# ShutdownLoop.net
KiCad netlist of a schematic drawn in Altium Designer
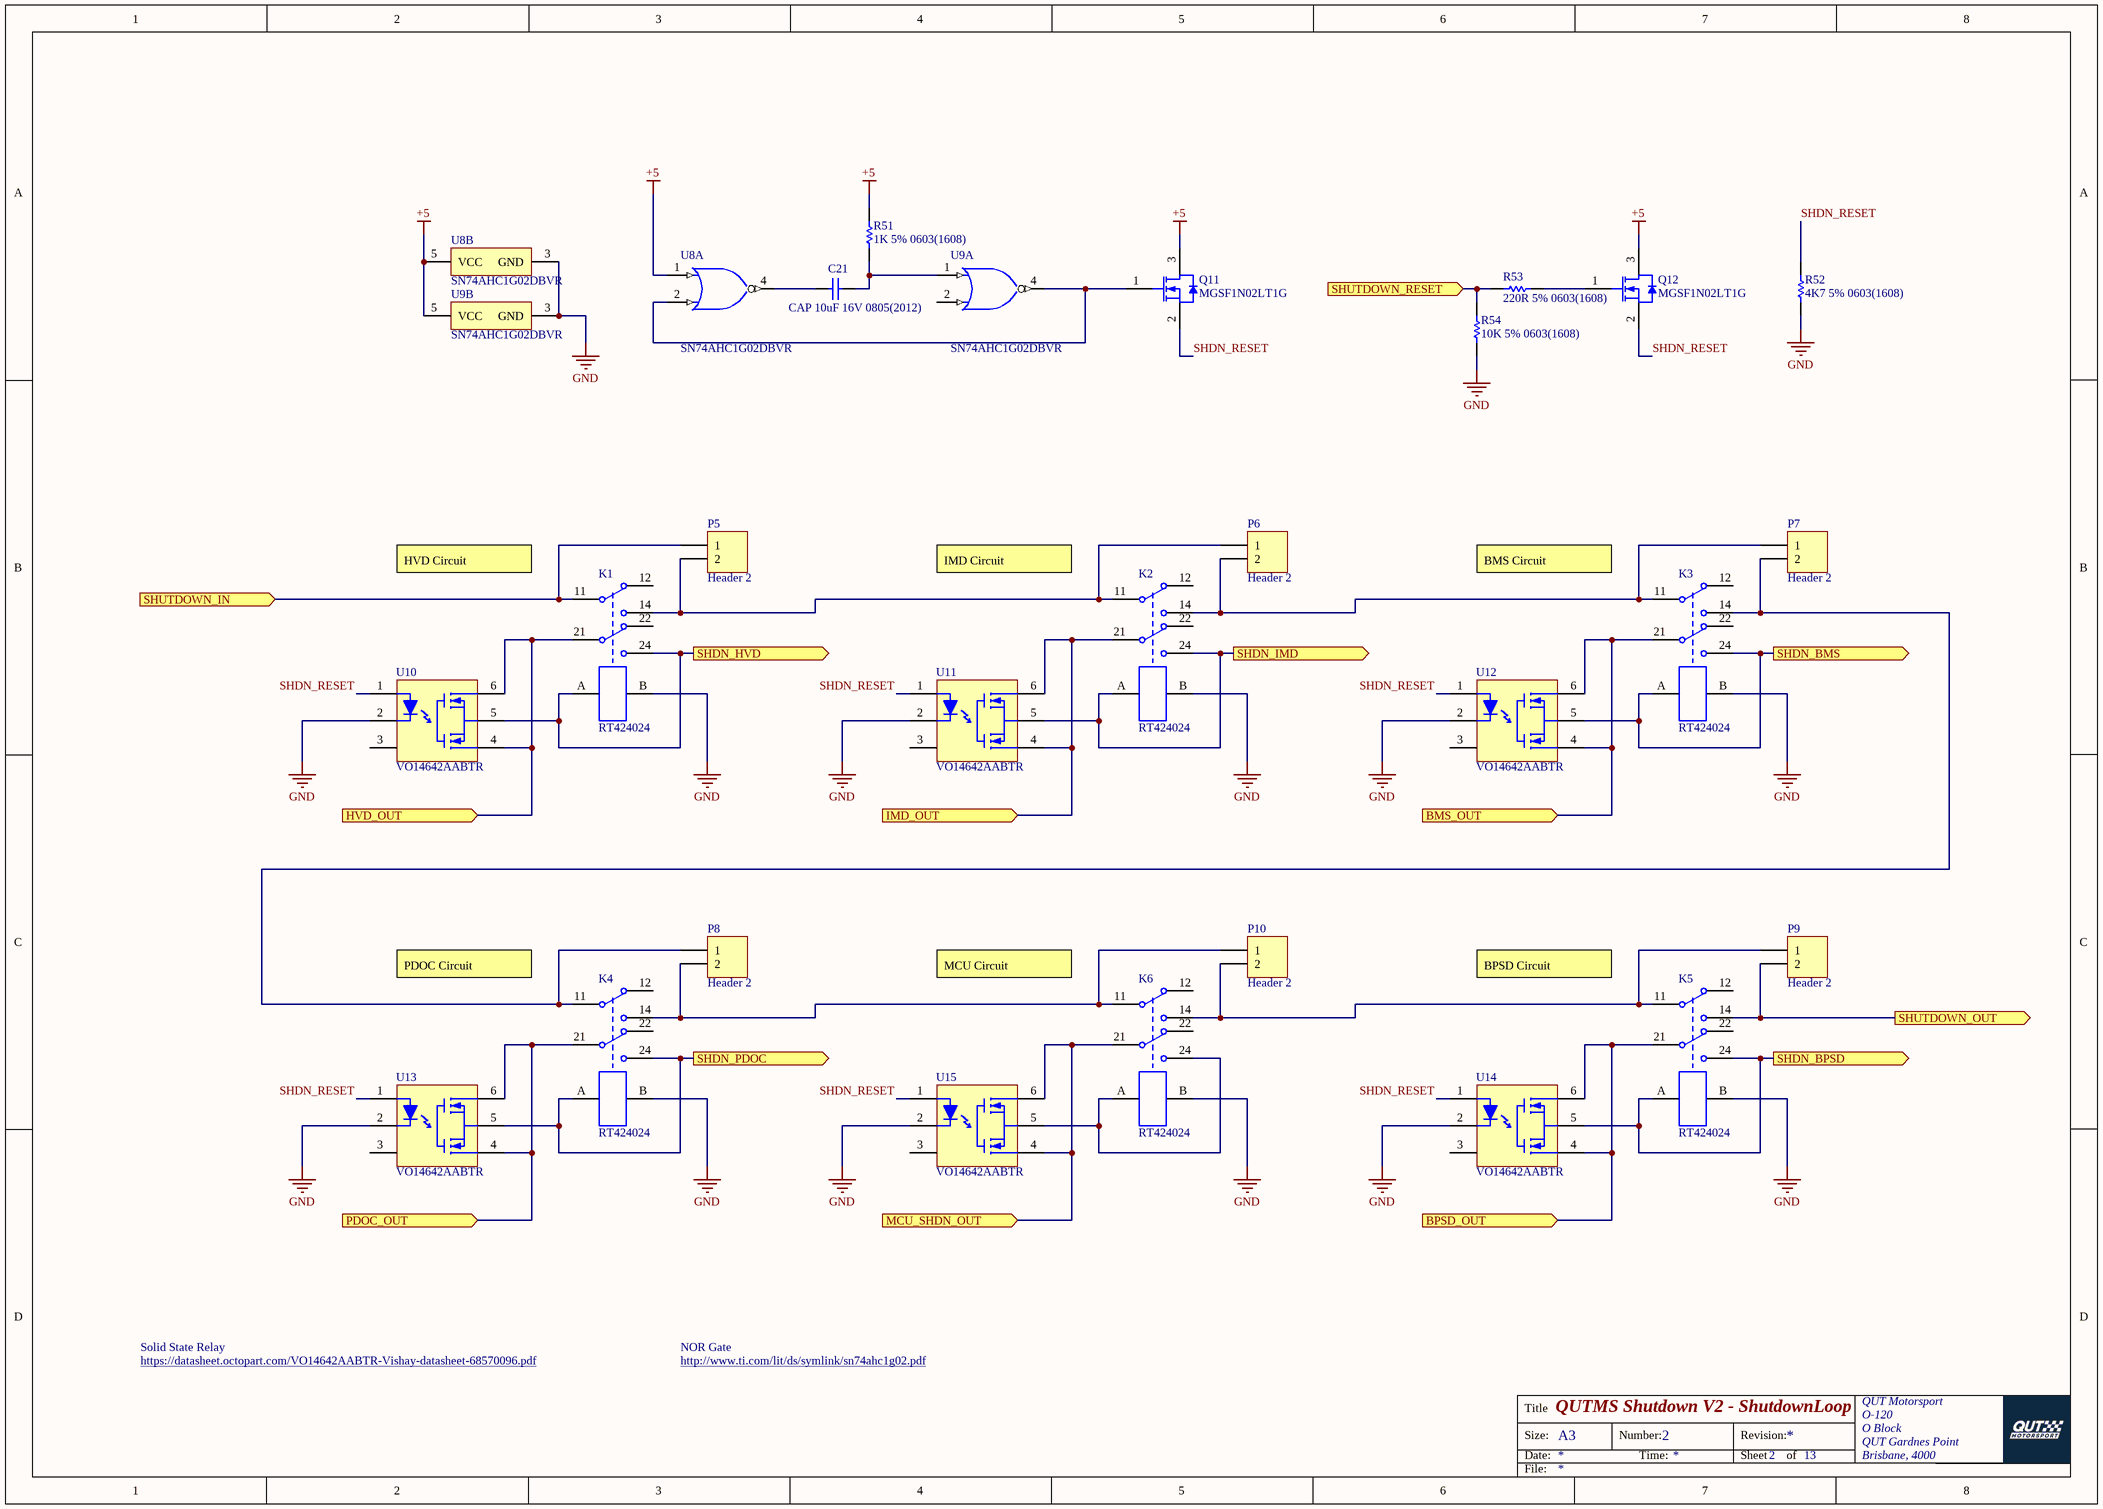
[diagram p0: ShutdownLoop.SchDoc]

(export (version "E")
  (design (tool "Eeschema 10.0.6"))
  (components
    (comp (ref "C21")
      (value "CAP 10uF 16V 0805(2012)")
      (footprint "CAPC0805(2012)100_L")
      (description "CAP 10uF 16V ±10% 0805 (2012 Metric) Thickness 1mm SMD")
      (fields (field (name "TOLERANCE") "Â±10%"))
      (libsource (lib "Altium Content Vault") (part "CAP"))
    )
    (comp (ref "K1")
      (value "RT424024")
      (footprint "TECO-RT424024_V")
      (description "DPDT 2 Form C (CO) Low Power PCB Relay, 24 VDC, 8 A, -40 to 85 degC, 8-Pin THD, RoHS, Tube")
      (fields (field (name "MANUFACTURER") "TE Connectivity"))
      (libsource (lib "Altium Content Vault") (part "RELAY-DPDT-8"))
    )
    (comp (ref "K2")
      (value "RT424024")
      (footprint "TECO-RT424024_V")
      (description "DPDT 2 Form C (CO) Low Power PCB Relay, 24 VDC, 8 A, -40 to 85 degC, 8-Pin THD, RoHS, Tube")
      (fields (field (name "MANUFACTURER") "TE Connectivity"))
      (libsource (lib "Altium Content Vault") (part "RELAY-DPDT-8"))
    )
    (comp (ref "K3")
      (value "RT424024")
      (footprint "TECO-RT424024_V")
      (description "DPDT 2 Form C (CO) Low Power PCB Relay, 24 VDC, 8 A, -40 to 85 degC, 8-Pin THD, RoHS, Tube")
      (fields (field (name "MANUFACTURER") "TE Connectivity"))
      (libsource (lib "Altium Content Vault") (part "RELAY-DPDT-8"))
    )
    (comp (ref "K4")
      (value "RT424024")
      (footprint "TECO-RT424024_V")
      (description "DPDT 2 Form C (CO) Low Power PCB Relay, 24 VDC, 8 A, -40 to 85 degC, 8-Pin THD, RoHS, Tube")
      (fields (field (name "MANUFACTURER") "TE Connectivity"))
      (libsource (lib "Altium Content Vault") (part "RELAY-DPDT-8"))
    )
    (comp (ref "K5")
      (value "RT424024")
      (footprint "TECO-RT424024_V")
      (description "DPDT 2 Form C (CO) Low Power PCB Relay, 24 VDC, 8 A, -40 to 85 degC, 8-Pin THD, RoHS, Tube")
      (fields (field (name "MANUFACTURER") "TE Connectivity"))
      (libsource (lib "Altium Content Vault") (part "RELAY-DPDT-8"))
    )
    (comp (ref "K6")
      (value "RT424024")
      (footprint "TECO-RT424024_V")
      (description "DPDT 2 Form C (CO) Low Power PCB Relay, 24 VDC, 8 A, -40 to 85 degC, 8-Pin THD, RoHS, Tube")
      (fields (field (name "MANUFACTURER") "TE Connectivity"))
      (libsource (lib "Altium Content Vault") (part "RELAY-DPDT-8"))
    )
    (comp (ref "P5")
      (value "Header 2")
      (footprint "HDR1X2")
      (description "Header, 2-Pin")
      (fields (field (name "PUBLISHER") "Altium Limited"))
      (libsource (lib "Miscellaneous Connectors") (part "Header 2"))
    )
    (comp (ref "P6")
      (value "Header 2")
      (footprint "HDR1X2")
      (description "Header, 2-Pin")
      (fields (field (name "PUBLISHER") "Altium Limited"))
      (libsource (lib "Miscellaneous Connectors") (part "Header 2"))
    )
    (comp (ref "P7")
      (value "Header 2")
      (footprint "HDR1X2")
      (description "Header, 2-Pin")
      (fields (field (name "PUBLISHER") "Altium Limited"))
      (libsource (lib "Miscellaneous Connectors") (part "Header 2"))
    )
    (comp (ref "P8")
      (value "Header 2")
      (footprint "HDR1X2")
      (description "Header, 2-Pin")
      (fields (field (name "PUBLISHER") "Altium Limited"))
      (libsource (lib "Miscellaneous Connectors") (part "Header 2"))
    )
    (comp (ref "P9")
      (value "Header 2")
      (footprint "HDR1X2")
      (description "Header, 2-Pin")
      (fields (field (name "PUBLISHER") "Altium Limited"))
      (libsource (lib "Miscellaneous Connectors") (part "Header 2"))
    )
    (comp (ref "P10")
      (value "Header 2")
      (footprint "HDR1X2")
      (description "Header, 2-Pin")
      (fields (field (name "PUBLISHER") "Altium Limited"))
      (libsource (lib "Miscellaneous Connectors") (part "Header 2"))
    )
    (comp (ref "Q11")
      (value "MGSF1N02LT1G")
      (footprint "ONSC-SOT-23-3-318-08_V")
      (description "Power MOSFET, 750 mA, 20 V, N-Channel, 3-Pin SOT-23, Pb-Free, Tape and Reel")
      (fields (field (name "MANUFACTURER") "On Semiconductor"))
      (libsource (lib "Altium Content Vault") (part "ONSC-NMOS-G1S2D3-3"))
    )
    (comp (ref "Q12")
      (value "MGSF1N02LT1G")
      (footprint "ONSC-SOT-23-3-318-08_V")
      (description "Power MOSFET, 750 mA, 20 V, N-Channel, 3-Pin SOT-23, Pb-Free, Tape and Reel")
      (fields (field (name "MANUFACTURER") "On Semiconductor"))
      (libsource (lib "Altium Content Vault") (part "ONSC-NMOS-G1S2D3-3"))
    )
    (comp (ref "R51")
      (value "1K 5% 0603(1608)")
      (footprint "RESC0603(1608)_L")
      (description "1K 0.1W 5% 0603 (1608 Metric)  SMD")
      (fields (field (name "TOLERANCE") "5 %") (field (name "POWER") "0.1 W"))
      (libsource (lib "Altium Content Vault") (part "RES"))
    )
    (comp (ref "R52")
      (value "4K7 5% 0603(1608)")
      (footprint "RESC0603(1608)_N")
      (description "4K7 0.1W 5% 0603 (1608 Metric)  SMD")
      (fields (field (name "TOLERANCE") "5 %") (field (name "POWER") "0.1 W"))
      (libsource (lib "Altium Content Vault") (part "RES"))
    )
    (comp (ref "R53")
      (value "220R 5% 0603(1608)")
      (footprint "RESC0603(1608)_M")
      (description "220R 0.1W 5% 0603 (1608 Metric)  SMD")
      (fields (field (name "POWER") "0.1 W") (field (name "TOLERANCE") "5 %"))
      (libsource (lib "Altium Content Vault") (part "RES"))
    )
    (comp (ref "R54")
      (value "10K 5% 0603(1608)")
      (footprint "RESC0603(1608)_N")
      (description "10K 0.1W 5% 0603 (1608 Metric)  SMD")
      (fields (field (name "TOLERANCE") "5 %") (field (name "POWER") "0.1 W"))
      (libsource (lib "Altium Content Vault") (part "RES"))
    )
    (comp (ref "U8")
      (value "SN74AHC1G02DBVR")
      (footprint "DBV0005A_L")
      (description "Single 2-Input Positive-NOR Gate, DBV0005A, LARGE T&R")
      (fields
        (field (name "MANUFACTURER") "Texas Instruments")
        (field (name "GENERIC PART NUMBER") "SN74AHC1G02")
      )
      (libsource (lib "Altium Content Vault") (part "TI-SN74XXX1X02-5"))
    )
    (comp (ref "U9")
      (value "SN74AHC1G02DBVR")
      (footprint "DBV0005A_L")
      (description "Single 2-Input Positive-NOR Gate, DBV0005A, LARGE T&R")
      (fields
        (field (name "MANUFACTURER") "Texas Instruments")
        (field (name "GENERIC PART NUMBER") "SN74AHC1G02")
      )
      (libsource (lib "Altium Content Vault") (part "TI-SN74XXX1X02-5"))
    )
    (comp (ref "U10")
      (value "VO14642AABTR")
      (footprint "VISH-VO14642AABTR_V")
      (description "1 Form A Solid State Relay, 2 A, -40 to 85 degC, 6-Pin SMD, RoHS, Tape and Reel")
      (fields (field (name "MANUFACTURER") "Vishay"))
      (libsource (lib "Altium Content Vault") (part "VISH-VO14642AABTR-6"))
    )
    (comp (ref "U11")
      (value "VO14642AABTR")
      (footprint "VISH-VO14642AABTR_V")
      (description "1 Form A Solid State Relay, 2 A, -40 to 85 degC, 6-Pin SMD, RoHS, Tape and Reel")
      (fields (field (name "MANUFACTURER") "Vishay"))
      (libsource (lib "Altium Content Vault") (part "VISH-VO14642AABTR-6"))
    )
    (comp (ref "U12")
      (value "VO14642AABTR")
      (footprint "VISH-VO14642AABTR_V")
      (description "1 Form A Solid State Relay, 2 A, -40 to 85 degC, 6-Pin SMD, RoHS, Tape and Reel")
      (fields (field (name "MANUFACTURER") "Vishay"))
      (libsource (lib "Altium Content Vault") (part "VISH-VO14642AABTR-6"))
    )
    (comp (ref "U13")
      (value "VO14642AABTR")
      (footprint "VISH-VO14642AABTR_V")
      (description "1 Form A Solid State Relay, 2 A, -40 to 85 degC, 6-Pin SMD, RoHS, Tape and Reel")
      (fields (field (name "MANUFACTURER") "Vishay"))
      (libsource (lib "Altium Content Vault") (part "VISH-VO14642AABTR-6"))
    )
    (comp (ref "U14")
      (value "VO14642AABTR")
      (footprint "VISH-VO14642AABTR_V")
      (description "1 Form A Solid State Relay, 2 A, -40 to 85 degC, 6-Pin SMD, RoHS, Tape and Reel")
      (fields (field (name "MANUFACTURER") "Vishay"))
      (libsource (lib "Altium Content Vault") (part "VISH-VO14642AABTR-6"))
    )
    (comp (ref "U15")
      (value "VO14642AABTR")
      (footprint "VISH-VO14642AABTR_V")
      (description "1 Form A Solid State Relay, 2 A, -40 to 85 degC, 6-Pin SMD, RoHS, Tape and Reel")
      (fields (field (name "MANUFACTURER") "Vishay"))
      (libsource (lib "Altium Content Vault") (part "VISH-VO14642AABTR-6"))
    )
  )
  (nets
    (net (code "1") (name "+5") (class "Default")
      (node (ref "Q11") (pin "3") (pinfunction "D_3") (pintype "passive"))
      (node (ref "Q12") (pin "3") (pinfunction "D_3") (pintype "passive"))
      (node (ref "R51") (pin "2") (pinfunction "2_2") (pintype "passive"))
      (node (ref "U8") (pin "1") (pinfunction "A_1") (pintype "input"))
      (node (ref "U8") (pin "5") (pinfunction "VCC_5") (pintype "power_in"))
      (node (ref "U9") (pin "5") (pinfunction "VCC_5") (pintype "power_in"))
    )
    (net (code "3") (name "/BMS_OUT") (class "Default")
      (node (ref "K3") (pin "21") (pinfunction "21_21") (pintype "passive"))
      (node (ref "U12") (pin "4") (pinfunction "S'_4") (pintype "passive"))
      (node (ref "U12") (pin "6") (pinfunction "S_6") (pintype "passive"))
    )
    (net (code "4") (name "/BPSD_OUT") (class "Default")
      (node (ref "K5") (pin "21") (pinfunction "21_21") (pintype "passive"))
      (node (ref "U14") (pin "4") (pinfunction "S'_4") (pintype "passive"))
      (node (ref "U14") (pin "6") (pinfunction "S_6") (pintype "passive"))
    )
    (net (code "5") (name "/HVD_OUT") (class "Default")
      (node (ref "K1") (pin "21") (pinfunction "21_21") (pintype "passive"))
      (node (ref "U10") (pin "4") (pinfunction "S'_4") (pintype "passive"))
      (node (ref "U10") (pin "6") (pinfunction "S_6") (pintype "passive"))
    )
    (net (code "6") (name "/IMD_OUT") (class "Default")
      (node (ref "K2") (pin "21") (pinfunction "21_21") (pintype "passive"))
      (node (ref "U11") (pin "4") (pinfunction "S'_4") (pintype "passive"))
      (node (ref "U11") (pin "6") (pinfunction "S_6") (pintype "passive"))
    )
    (net (code "7") (name "/MCU_SHDN_OUT") (class "Default")
      (node (ref "K6") (pin "21") (pinfunction "21_21") (pintype "passive"))
      (node (ref "U15") (pin "4") (pinfunction "S'_4") (pintype "passive"))
      (node (ref "U15") (pin "6") (pinfunction "S_6") (pintype "passive"))
    )
    (net (code "8") (name "/PDOC_OUT") (class "Default")
      (node (ref "K4") (pin "21") (pinfunction "21_21") (pintype "passive"))
      (node (ref "U13") (pin "4") (pinfunction "S'_4") (pintype "passive"))
      (node (ref "U13") (pin "6") (pinfunction "S_6") (pintype "passive"))
    )
    (net (code "9") (name "/SHDN_BMS") (class "Default")
      (node (ref "K3") (pin "24") (pinfunction "24_24") (pintype "passive"))
      (node (ref "K3") (pin "A") (pinfunction "A_A") (pintype "passive"))
      (node (ref "U12") (pin "5") (pinfunction "DC_5") (pintype "passive"))
    )
    (net (code "10") (name "/SHDN_BPSD") (class "Default")
      (node (ref "K5") (pin "24") (pinfunction "24_24") (pintype "passive"))
      (node (ref "K5") (pin "A") (pinfunction "A_A") (pintype "passive"))
      (node (ref "U14") (pin "5") (pinfunction "DC_5") (pintype "passive"))
    )
    (net (code "11") (name "/SHDN_HVD") (class "Default")
      (node (ref "K1") (pin "24") (pinfunction "24_24") (pintype "passive"))
      (node (ref "K1") (pin "A") (pinfunction "A_A") (pintype "passive"))
      (node (ref "U10") (pin "5") (pinfunction "DC_5") (pintype "passive"))
    )
    (net (code "12") (name "/SHDN_IMD") (class "Default")
      (node (ref "K2") (pin "24") (pinfunction "24_24") (pintype "passive"))
      (node (ref "K2") (pin "A") (pinfunction "A_A") (pintype "passive"))
      (node (ref "U11") (pin "5") (pinfunction "DC_5") (pintype "passive"))
    )
    (net (code "13") (name "/SHDN_PDOC") (class "Default")
      (node (ref "K4") (pin "24") (pinfunction "24_24") (pintype "passive"))
      (node (ref "K4") (pin "A") (pinfunction "A_A") (pintype "passive"))
      (node (ref "U13") (pin "5") (pinfunction "DC_5") (pintype "passive"))
    )
    (net (code "14") (name "/SHDN_RESET") (class "Default")
      (node (ref "Q11") (pin "2") (pinfunction "S_2") (pintype "passive"))
      (node (ref "Q12") (pin "2") (pinfunction "S_2") (pintype "passive"))
      (node (ref "R52") (pin "2") (pinfunction "2_2") (pintype "passive"))
      (node (ref "U10") (pin "1") (pinfunction "A_1") (pintype "passive"))
      (node (ref "U11") (pin "1") (pinfunction "A_1") (pintype "passive"))
      (node (ref "U12") (pin "1") (pinfunction "A_1") (pintype "passive"))
      (node (ref "U13") (pin "1") (pinfunction "A_1") (pintype "passive"))
      (node (ref "U14") (pin "1") (pinfunction "A_1") (pintype "passive"))
      (node (ref "U15") (pin "1") (pinfunction "A_1") (pintype "passive"))
    )
    (net (code "15") (name "/SHUTDOWN_IN") (class "Default")
      (node (ref "K1") (pin "11") (pinfunction "11_11") (pintype "passive"))
      (node (ref "P5") (pin "1") (pinfunction "1_1") (pintype "passive"))
    )
    (net (code "16") (name "/SHUTDOWN_OUT") (class "Default")
      (node (ref "K5") (pin "14") (pinfunction "14_14") (pintype "passive"))
      (node (ref "P9") (pin "2") (pinfunction "2_2") (pintype "passive"))
    )
    (net (code "17") (name "/SHUTDOWN_RESET") (class "Default")
      (node (ref "R53") (pin "1") (pinfunction "1_1") (pintype "passive"))
      (node (ref "R54") (pin "2") (pinfunction "2_2") (pintype "passive"))
    )
    (net (code "18") (name "GND") (class "Default")
      (node (ref "K1") (pin "B") (pinfunction "B_B") (pintype "passive"))
      (node (ref "K2") (pin "B") (pinfunction "B_B") (pintype "passive"))
      (node (ref "K3") (pin "B") (pinfunction "B_B") (pintype "passive"))
      (node (ref "K4") (pin "B") (pinfunction "B_B") (pintype "passive"))
      (node (ref "K5") (pin "B") (pinfunction "B_B") (pintype "passive"))
      (node (ref "K6") (pin "B") (pinfunction "B_B") (pintype "passive"))
      (node (ref "R52") (pin "1") (pinfunction "1_1") (pintype "passive"))
      (node (ref "R54") (pin "1") (pinfunction "1_1") (pintype "passive"))
      (node (ref "U10") (pin "2") (pinfunction "K_2") (pintype "passive"))
      (node (ref "U11") (pin "2") (pinfunction "K_2") (pintype "passive"))
      (node (ref "U12") (pin "2") (pinfunction "K_2") (pintype "passive"))
      (node (ref "U13") (pin "2") (pinfunction "K_2") (pintype "passive"))
      (node (ref "U14") (pin "2") (pinfunction "K_2") (pintype "passive"))
      (node (ref "U15") (pin "2") (pinfunction "K_2") (pintype "passive"))
      (node (ref "U8") (pin "3") (pinfunction "GND_3") (pintype "power_in"))
      (node (ref "U9") (pin "3") (pinfunction "GND_3") (pintype "power_in"))
    )
    (net (code "19") (name "Net-(K1-Pad14)") (class "Default")
      (node (ref "K1") (pin "14") (pinfunction "14_14") (pintype "passive"))
      (node (ref "K2") (pin "11") (pinfunction "11_11") (pintype "passive"))
      (node (ref "P5") (pin "2") (pinfunction "2_2") (pintype "passive"))
      (node (ref "P6") (pin "1") (pinfunction "1_1") (pintype "passive"))
    )
    (net (code "20") (name "Net-(K2-Pad14)") (class "Default")
      (node (ref "K2") (pin "14") (pinfunction "14_14") (pintype "passive"))
      (node (ref "K3") (pin "11") (pinfunction "11_11") (pintype "passive"))
      (node (ref "P6") (pin "2") (pinfunction "2_2") (pintype "passive"))
      (node (ref "P7") (pin "1") (pinfunction "1_1") (pintype "passive"))
    )
    (net (code "21") (name "Net-(K3-Pad14)") (class "Default")
      (node (ref "K3") (pin "14") (pinfunction "14_14") (pintype "passive"))
      (node (ref "K4") (pin "11") (pinfunction "11_11") (pintype "passive"))
      (node (ref "P7") (pin "2") (pinfunction "2_2") (pintype "passive"))
      (node (ref "P8") (pin "1") (pinfunction "1_1") (pintype "passive"))
    )
    (net (code "22") (name "Net-(K4-Pad14)") (class "Default")
      (node (ref "K4") (pin "14") (pinfunction "14_14") (pintype "passive"))
      (node (ref "K6") (pin "11") (pinfunction "11_11") (pintype "passive"))
      (node (ref "P10") (pin "1") (pinfunction "1_1") (pintype "passive"))
      (node (ref "P8") (pin "2") (pinfunction "2_2") (pintype "passive"))
    )
    (net (code "23") (name "Net-(K5-Pad11)") (class "Default")
      (node (ref "K5") (pin "11") (pinfunction "11_11") (pintype "passive"))
      (node (ref "K6") (pin "14") (pinfunction "14_14") (pintype "passive"))
      (node (ref "P10") (pin "2") (pinfunction "2_2") (pintype "passive"))
      (node (ref "P9") (pin "1") (pinfunction "1_1") (pintype "passive"))
    )
    (net (code "24") (name "Net-(Q11-G)") (class "Default")
      (node (ref "Q11") (pin "1") (pinfunction "G_1") (pintype "passive"))
      (node (ref "U8") (pin "2") (pinfunction "B_2") (pintype "input"))
      (node (ref "U9") (pin "4") (pinfunction "Y_4") (pintype "output"))
    )
    (net (code "25") (name "Net-(Q12-G)") (class "Default")
      (node (ref "Q12") (pin "1") (pinfunction "G_1") (pintype "passive"))
      (node (ref "R53") (pin "2") (pinfunction "2_2") (pintype "passive"))
    )
    (net (code "26") (name "Net-(U8A-Y)") (class "Default")
      (node (ref "C21") (pin "1") (pinfunction "1_1") (pintype "passive"))
      (node (ref "U8") (pin "4") (pinfunction "Y_4") (pintype "output"))
    )
    (net (code "27") (name "Net-(U9A-A)") (class "Default")
      (node (ref "C21") (pin "2") (pinfunction "2_2") (pintype "passive"))
      (node (ref "R51") (pin "1") (pinfunction "1_1") (pintype "passive"))
      (node (ref "U9") (pin "1") (pinfunction "A_1") (pintype "input"))
    )
    (net (code "28") (name "Net-(U15-DC)") (class "Default")
      (node (ref "K6") (pin "24") (pinfunction "24_24") (pintype "passive"))
      (node (ref "K6") (pin "A") (pinfunction "A_A") (pintype "passive"))
      (node (ref "U15") (pin "5") (pinfunction "DC_5") (pintype "passive"))
    )
    (net (code "29") (name "unconnected-(K1-Pad12)") (class "Default")
      (node (ref "K1") (pin "12") (pinfunction "12_12") (pintype "passive"))
    )
    (net (code "30") (name "unconnected-(K1-Pad22)") (class "Default")
      (node (ref "K1") (pin "22") (pinfunction "22_22") (pintype "passive"))
    )
    (net (code "31") (name "unconnected-(K2-Pad12)") (class "Default")
      (node (ref "K2") (pin "12") (pinfunction "12_12") (pintype "passive"))
    )
    (net (code "32") (name "unconnected-(K2-Pad22)") (class "Default")
      (node (ref "K2") (pin "22") (pinfunction "22_22") (pintype "passive"))
    )
    (net (code "33") (name "unconnected-(K3-Pad12)") (class "Default")
      (node (ref "K3") (pin "12") (pinfunction "12_12") (pintype "passive"))
    )
    (net (code "34") (name "unconnected-(K3-Pad22)") (class "Default")
      (node (ref "K3") (pin "22") (pinfunction "22_22") (pintype "passive"))
    )
    (net (code "35") (name "unconnected-(K4-Pad12)") (class "Default")
      (node (ref "K4") (pin "12") (pinfunction "12_12") (pintype "passive"))
    )
    (net (code "36") (name "unconnected-(K4-Pad22)") (class "Default")
      (node (ref "K4") (pin "22") (pinfunction "22_22") (pintype "passive"))
    )
    (net (code "37") (name "unconnected-(K5-Pad12)") (class "Default")
      (node (ref "K5") (pin "12") (pinfunction "12_12") (pintype "passive"))
    )
    (net (code "38") (name "unconnected-(K5-Pad22)") (class "Default")
      (node (ref "K5") (pin "22") (pinfunction "22_22") (pintype "passive"))
    )
    (net (code "39") (name "unconnected-(K6-Pad12)") (class "Default")
      (node (ref "K6") (pin "12") (pinfunction "12_12") (pintype "passive"))
    )
    (net (code "40") (name "unconnected-(K6-Pad22)") (class "Default")
      (node (ref "K6") (pin "22") (pinfunction "22_22") (pintype "passive"))
    )
    (net (code "41") (name "unconnected-(U9A-B-Pad2)") (class "Default")
      (node (ref "U9") (pin "2") (pinfunction "B_2") (pintype "input"))
    )
    (net (code "42") (name "unconnected-(U10-NC-Pad3)") (class "Default")
      (node (ref "U10") (pin "3") (pinfunction "NC_3") (pintype "passive"))
    )
    (net (code "43") (name "unconnected-(U11-NC-Pad3)") (class "Default")
      (node (ref "U11") (pin "3") (pinfunction "NC_3") (pintype "passive"))
    )
    (net (code "44") (name "unconnected-(U12-NC-Pad3)") (class "Default")
      (node (ref "U12") (pin "3") (pinfunction "NC_3") (pintype "passive"))
    )
    (net (code "45") (name "unconnected-(U13-NC-Pad3)") (class "Default")
      (node (ref "U13") (pin "3") (pinfunction "NC_3") (pintype "passive"))
    )
    (net (code "46") (name "unconnected-(U14-NC-Pad3)") (class "Default")
      (node (ref "U14") (pin "3") (pinfunction "NC_3") (pintype "passive"))
    )
    (net (code "47") (name "unconnected-(U15-NC-Pad3)") (class "Default")
      (node (ref "U15") (pin "3") (pinfunction "NC_3") (pintype "passive"))
    )
  )
)
